# KitchenTimer_v2.net
KiCad netlist of a schematic drawn in EAGLE
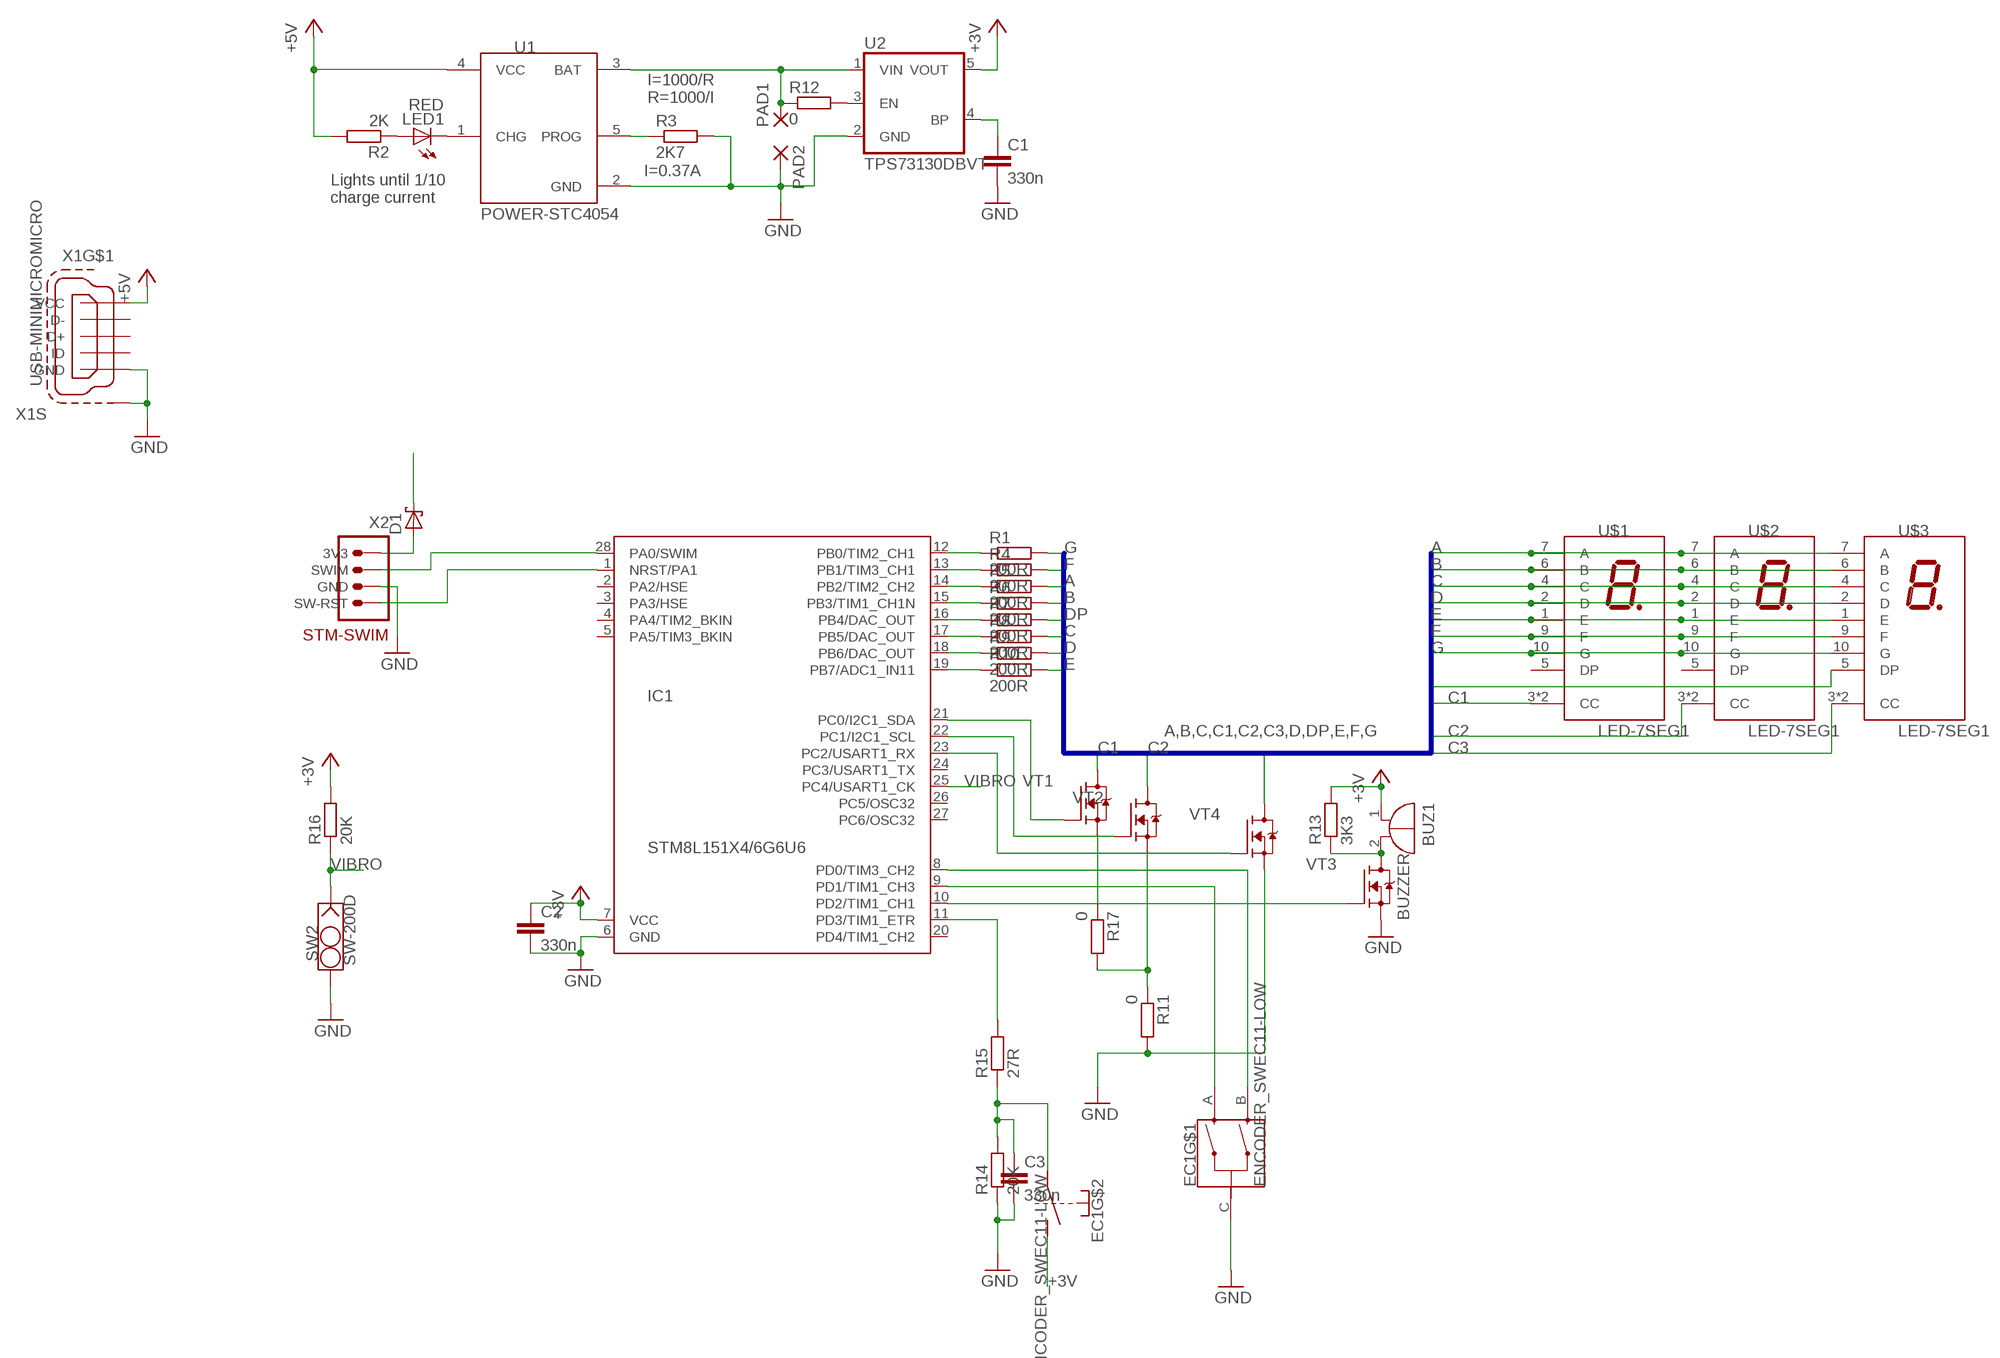
[diagram p0: schematic, sheet 1]

(export (version "E")
  (design (tool "Eeschema 10.0.6"))
  (components
    (comp (ref "BUZ1")
      (value "BUZZER")
      (footprint "eagle-import:PIEZO-D12_H9")
      (libsource (lib "eagle-import") (part "BUZZER"))
    )
    (comp (ref "C1")
      (value "330n")
      (footprint "eagle-import:CAP1206")
      (libsource (lib "eagle-import") (part "CAP_1206"))
    )
    (comp (ref "C2")
      (value "330n")
      (footprint "eagle-import:CAP1206")
      (libsource (lib "eagle-import") (part "CAP_1206"))
    )
    (comp (ref "C3")
      (value "330n")
      (footprint "eagle-import:CAP1206")
      (libsource (lib "eagle-import") (part "CAP_1206"))
    )
    (comp (ref "D1")
      (value "DIODE-SH_SOD523")
      (footprint "eagle-import:SODFL1608X65")
      (libsource (lib "eagle-import") (part "DIODE-SH_SOD523"))
    )
    (comp (ref "EC1")
      (value "ENCODER_SWEC11-LOW")
      (footprint "eagle-import:EC11E1544505")
      (libsource (lib "eagle-import") (part "ENCODER_SWEC11-LOW"))
    )
    (comp (ref "IC1")
      (value "STM8L151X4/6G6U6")
      (footprint "eagle-import:QFN28")
      (libsource (lib "eagle-import") (part "STM8L151X4/6G6U6"))
    )
    (comp (ref "LED1")
      (value "RED")
      (footprint "eagle-import:LED1206")
      (libsource (lib "eagle-import") (part "LED_1206"))
    )
    (comp (ref "PAD1")
      (value "1,6/0,9")
      (footprint "eagle-import:1,6_0,9")
      (libsource (lib "eagle-import") (part "1,6/0,9"))
    )
    (comp (ref "PAD2")
      (value "1,6/0,9")
      (footprint "eagle-import:1,6_0,9")
      (libsource (lib "eagle-import") (part "1,6/0,9"))
    )
    (comp (ref "R1")
      (value "200R")
      (footprint "eagle-import:RESC2012X50")
      (libsource (lib "eagle-import") (part "R_R0805"))
    )
    (comp (ref "R2")
      (value "2K")
      (footprint "eagle-import:RESC2012X50")
      (libsource (lib "eagle-import") (part "R_R0805"))
    )
    (comp (ref "R3")
      (value "2K7")
      (footprint "eagle-import:RESC2012X50")
      (libsource (lib "eagle-import") (part "R_R0805"))
    )
    (comp (ref "R4")
      (value "200R")
      (footprint "eagle-import:RESC2012X50")
      (libsource (lib "eagle-import") (part "R_R0805"))
    )
    (comp (ref "R5")
      (value "200R")
      (footprint "eagle-import:RESC2012X50")
      (libsource (lib "eagle-import") (part "R_R0805"))
    )
    (comp (ref "R6")
      (value "200R")
      (footprint "eagle-import:RESC2012X50")
      (libsource (lib "eagle-import") (part "R_R0805"))
    )
    (comp (ref "R7")
      (value "200R")
      (footprint "eagle-import:RESC2012X50")
      (libsource (lib "eagle-import") (part "R_R0805"))
    )
    (comp (ref "R8")
      (value "200R")
      (footprint "eagle-import:RESC2012X50")
      (libsource (lib "eagle-import") (part "R_R0805"))
    )
    (comp (ref "R9")
      (value "200R")
      (footprint "eagle-import:RESC2012X50")
      (libsource (lib "eagle-import") (part "R_R0805"))
    )
    (comp (ref "R10")
      (value "200R")
      (footprint "eagle-import:RESC2012X50")
      (libsource (lib "eagle-import") (part "R_R0805"))
    )
    (comp (ref "R11")
      (value "0")
      (footprint "eagle-import:RESC2012X50")
      (libsource (lib "eagle-import") (part "R_R0805"))
    )
    (comp (ref "R12")
      (value "0")
      (footprint "eagle-import:RESC2012X50")
      (libsource (lib "eagle-import") (part "R_R0805"))
    )
    (comp (ref "R13")
      (value "3K3")
      (footprint "eagle-import:RESC3216X60")
      (libsource (lib "eagle-import") (part "R_R1206"))
    )
    (comp (ref "R14")
      (value "20K")
      (footprint "eagle-import:RESC3216X60")
      (libsource (lib "eagle-import") (part "R_R1206"))
    )
    (comp (ref "R15")
      (value "27R")
      (footprint "eagle-import:RESC3216X60")
      (libsource (lib "eagle-import") (part "R_R1206"))
    )
    (comp (ref "R16")
      (value "20K")
      (footprint "eagle-import:RESC3216X60")
      (libsource (lib "eagle-import") (part "R_R1206"))
    )
    (comp (ref "R17")
      (value "0")
      (footprint "eagle-import:RESC2012X50")
      (libsource (lib "eagle-import") (part "R_R0805"))
    )
    (comp (ref "SW2")
      (value "SW-200D")
      (footprint "eagle-import:SW-200D")
      (libsource (lib "eagle-import") (part "SW-200D"))
    )
    (comp (ref "U$1")
      (value "LED-7SEG1")
      (footprint "eagle-import:LED-7SEG1")
      (libsource (lib "eagle-import") (part "LED-7SEG1"))
    )
    (comp (ref "U$2")
      (value "LED-7SEG1")
      (footprint "eagle-import:LED-7SEG1")
      (libsource (lib "eagle-import") (part "LED-7SEG1"))
    )
    (comp (ref "U$3")
      (value "LED-7SEG1")
      (footprint "eagle-import:LED-7SEG1")
      (libsource (lib "eagle-import") (part "LED-7SEG1"))
    )
    (comp (ref "U1")
      (value "POWER-STC4054")
      (footprint "eagle-import:SOT95P280X145-5")
      (libsource (lib "eagle-import") (part "POWER-STC4054"))
    )
    (comp (ref "U2")
      (value "TPS73130DBVT")
      (footprint "eagle-import:SOT95P280X145-5")
      (libsource (lib "eagle-import") (part "VREG-LD2985"))
    )
    (comp (ref "VT1")
      (value "FET-NSOT-23")
      (footprint "eagle-import:SOT95P240X115-3")
      (libsource (lib "eagle-import") (part "FET-NSOT-23"))
    )
    (comp (ref "VT2")
      (value "FET-NSOT-23")
      (footprint "eagle-import:SOT95P240X115-3")
      (libsource (lib "eagle-import") (part "FET-NSOT-23"))
    )
    (comp (ref "VT3")
      (value "FET-NSOT-23")
      (footprint "eagle-import:SOT95P240X115-3")
      (libsource (lib "eagle-import") (part "FET-NSOT-23"))
    )
    (comp (ref "VT4")
      (value "FET-NSOT-23")
      (footprint "eagle-import:SOT95P240X115-3")
      (libsource (lib "eagle-import") (part "FET-NSOT-23"))
    )
    (comp (ref "X1")
      (value "USB-MINIMICROMICRO")
      (footprint "eagle-import:USB-B-MICRO-SMD")
      (libsource (lib "eagle-import") (part "USB-MINIMICROMICRO"))
    )
    (comp (ref "X2")
      (value "STM-SWIMPOGOPADS")
      (footprint "eagle-import:SWIM-PADS-1.27")
      (libsource (lib "eagle-import") (part "STM-SWIMPOGOPADS"))
    )
  )
  (nets
    (net (code "1") (name "+3V") (class "Default")
      (node (ref "BUZ1") (pin "1") (pinfunction "+_1") (pintype "passive"))
      (node (ref "C2") (pin "1") (pinfunction "1_1") (pintype "passive"))
      (node (ref "D1") (pin "1") (pinfunction "C_1") (pintype "passive"))
      (node (ref "EC1") (pin "E") (pinfunction "2_E") (pintype "passive"))
      (node (ref "IC1") (pin "7") (pinfunction "VCC_7") (pintype "power_in"))
      (node (ref "R13") (pin "2") (pinfunction "2_2") (pintype "passive"))
      (node (ref "R16") (pin "2") (pinfunction "2_2") (pintype "passive"))
      (node (ref "U2") (pin "5") (pinfunction "VOUT_5") (pintype "passive"))
    )
    (net (code "2") (name "+5V") (class "Default")
      (node (ref "R2") (pin "2") (pinfunction "2_2") (pintype "passive"))
      (node (ref "U1") (pin "4") (pinfunction "VCC_4") (pintype "power_in"))
      (node (ref "X1") (pin "VBUS") (pinfunction "VCC_VBUS") (pintype "passive"))
    )
    (net (code "3") (name "/A") (class "Default")
      (node (ref "R5") (pin "2") (pinfunction "2_2") (pintype "passive"))
      (node (ref "U$1") (pin "7") (pinfunction "A_7") (pintype "bidirectional"))
      (node (ref "U$2") (pin "7") (pinfunction "A_7") (pintype "bidirectional"))
      (node (ref "U$3") (pin "7") (pinfunction "A_7") (pintype "bidirectional"))
    )
    (net (code "4") (name "/B") (class "Default")
      (node (ref "R6") (pin "2") (pinfunction "2_2") (pintype "passive"))
      (node (ref "U$1") (pin "6") (pinfunction "B_6") (pintype "bidirectional"))
      (node (ref "U$2") (pin "6") (pinfunction "B_6") (pintype "bidirectional"))
      (node (ref "U$3") (pin "6") (pinfunction "B_6") (pintype "bidirectional"))
    )
    (net (code "5") (name "/C") (class "Default")
      (node (ref "R8") (pin "2") (pinfunction "2_2") (pintype "passive"))
      (node (ref "U$1") (pin "4") (pinfunction "C_4") (pintype "bidirectional"))
      (node (ref "U$2") (pin "4") (pinfunction "C_4") (pintype "bidirectional"))
      (node (ref "U$3") (pin "4") (pinfunction "C_4") (pintype "bidirectional"))
    )
    (net (code "6") (name "/C1") (class "Default")
      (node (ref "U$1") (pin "3") (pinfunction "CC_3") (pintype "bidirectional"))
      (node (ref "U$1") (pin "8") (pinfunction "CC_8") (pintype "bidirectional"))
      (node (ref "VT1") (pin "3") (pinfunction "D_3") (pintype "passive"))
    )
    (net (code "7") (name "/C2") (class "Default")
      (node (ref "U$2") (pin "3") (pinfunction "CC_3") (pintype "bidirectional"))
      (node (ref "U$2") (pin "8") (pinfunction "CC_8") (pintype "bidirectional"))
      (node (ref "VT2") (pin "3") (pinfunction "D_3") (pintype "passive"))
    )
    (net (code "8") (name "/C3") (class "Default")
      (node (ref "U$3") (pin "3") (pinfunction "CC_3") (pintype "bidirectional"))
      (node (ref "U$3") (pin "8") (pinfunction "CC_8") (pintype "bidirectional"))
      (node (ref "VT4") (pin "3") (pinfunction "D_3") (pintype "passive"))
    )
    (net (code "9") (name "/D") (class "Default")
      (node (ref "R9") (pin "2") (pinfunction "2_2") (pintype "passive"))
      (node (ref "U$1") (pin "2") (pinfunction "D_2") (pintype "bidirectional"))
      (node (ref "U$2") (pin "2") (pinfunction "D_2") (pintype "bidirectional"))
      (node (ref "U$3") (pin "2") (pinfunction "D_2") (pintype "bidirectional"))
    )
    (net (code "10") (name "/DP") (class "Default")
      (node (ref "R7") (pin "2") (pinfunction "2_2") (pintype "passive"))
      (node (ref "U$3") (pin "5") (pinfunction "DP_5") (pintype "bidirectional"))
    )
    (net (code "11") (name "/E") (class "Default")
      (node (ref "R10") (pin "2") (pinfunction "2_2") (pintype "passive"))
      (node (ref "U$1") (pin "1") (pinfunction "E_1") (pintype "bidirectional"))
      (node (ref "U$2") (pin "1") (pinfunction "E_1") (pintype "bidirectional"))
      (node (ref "U$3") (pin "1") (pinfunction "E_1") (pintype "bidirectional"))
    )
    (net (code "12") (name "/F") (class "Default")
      (node (ref "R4") (pin "2") (pinfunction "2_2") (pintype "passive"))
      (node (ref "U$1") (pin "9") (pinfunction "F_9") (pintype "bidirectional"))
      (node (ref "U$2") (pin "9") (pinfunction "F_9") (pintype "bidirectional"))
      (node (ref "U$3") (pin "9") (pinfunction "F_9") (pintype "bidirectional"))
    )
    (net (code "13") (name "/G") (class "Default")
      (node (ref "R1") (pin "2") (pinfunction "2_2") (pintype "passive"))
      (node (ref "U$1") (pin "10") (pinfunction "G_10") (pintype "bidirectional"))
      (node (ref "U$2") (pin "10") (pinfunction "G_10") (pintype "bidirectional"))
      (node (ref "U$3") (pin "10") (pinfunction "G_10") (pintype "bidirectional"))
    )
    (net (code "14") (name "/VIBRO") (class "Default")
      (node (ref "IC1") (pin "25") (pinfunction "PC4/USART1_CK_25") (pintype "bidirectional"))
      (node (ref "R16") (pin "1") (pinfunction "1_1") (pintype "passive"))
      (node (ref "SW2") (pin "G") (pinfunction "G_G") (pintype "bidirectional"))
    )
    (net (code "15") (name "GND") (class "Default")
      (node (ref "C1") (pin "2") (pinfunction "2_2") (pintype "passive"))
      (node (ref "C2") (pin "2") (pinfunction "2_2") (pintype "passive"))
      (node (ref "C3") (pin "2") (pinfunction "2_2") (pintype "passive"))
      (node (ref "EC1") (pin "C") (pinfunction "C_C") (pintype "bidirectional"))
      (node (ref "IC1") (pin "6") (pinfunction "GND_6") (pintype "power_in"))
      (node (ref "PAD2") (pin "1") (pinfunction "P_1") (pintype "passive"))
      (node (ref "R11") (pin "2") (pinfunction "2_2") (pintype "passive"))
      (node (ref "R14") (pin "1") (pinfunction "1_1") (pintype "passive"))
      (node (ref "R3") (pin "2") (pinfunction "2_2") (pintype "passive"))
      (node (ref "SW2") (pin "S") (pinfunction "S_S") (pintype "bidirectional"))
      (node (ref "U1") (pin "2") (pinfunction "GND_2") (pintype "power_in"))
      (node (ref "U2") (pin "2") (pinfunction "GND_2") (pintype "passive"))
      (node (ref "VT3") (pin "2") (pinfunction "S_2") (pintype "passive"))
      (node (ref "VT4") (pin "2") (pinfunction "S_2") (pintype "passive"))
      (node (ref "X1") (pin "GND") (pinfunction "GND_GND") (pintype "passive"))
      (node (ref "X1") (pin "SHIELD1") (pinfunction "S1_SHIELD1") (pintype "passive"))
      (node (ref "X1") (pin "SHIELD2") (pinfunction "S1_SHIELD2") (pintype "passive"))
      (node (ref "X1") (pin "SHIELD3") (pinfunction "S1_SHIELD3") (pintype "passive"))
      (node (ref "X2") (pin "P$3") (pinfunction "GND_P$3") (pintype "passive"))
    )
    (net (code "16") (name "Net-(BUZ1--)") (class "Default")
      (node (ref "BUZ1") (pin "2") (pinfunction "-_2") (pintype "passive"))
      (node (ref "R13") (pin "1") (pinfunction "1_1") (pintype "passive"))
      (node (ref "VT3") (pin "3") (pinfunction "D_3") (pintype "passive"))
    )
    (net (code "17") (name "Net-(D1-A)") (class "Default")
      (node (ref "D1") (pin "2") (pinfunction "A_2") (pintype "passive"))
      (node (ref "X2") (pin "P$1") (pinfunction "3V3_P$1") (pintype "passive"))
    )
    (net (code "18") (name "Net-(EC1B-1)") (class "Default")
      (node (ref "C3") (pin "1") (pinfunction "1_1") (pintype "passive"))
      (node (ref "EC1") (pin "D") (pinfunction "1_D") (pintype "passive"))
      (node (ref "R14") (pin "2") (pinfunction "2_2") (pintype "passive"))
      (node (ref "R15") (pin "1") (pinfunction "1_1") (pintype "passive"))
    )
    (net (code "19") (name "Net-(IC1-NRST{slash}PA1)") (class "Default")
      (node (ref "IC1") (pin "1") (pinfunction "NRST/PA1_1") (pintype "bidirectional"))
      (node (ref "X2") (pin "P$4") (pinfunction "SW-RST_P$4") (pintype "passive"))
    )
    (net (code "20") (name "Net-(IC1-PA0{slash}SWIM)") (class "Default")
      (node (ref "IC1") (pin "28") (pinfunction "PA0/SWIM_28") (pintype "bidirectional"))
      (node (ref "X2") (pin "P$2") (pinfunction "SWIM_P$2") (pintype "passive"))
    )
    (net (code "21") (name "Net-(IC1-PB0{slash}TIM2_CH1)") (class "Default")
      (node (ref "IC1") (pin "12") (pinfunction "PB0/TIM2_CH1_12") (pintype "bidirectional"))
      (node (ref "R1") (pin "1") (pinfunction "1_1") (pintype "passive"))
    )
    (net (code "22") (name "Net-(IC1-PB1{slash}TIM3_CH1)") (class "Default")
      (node (ref "IC1") (pin "13") (pinfunction "PB1/TIM3_CH1_13") (pintype "bidirectional"))
      (node (ref "R4") (pin "1") (pinfunction "1_1") (pintype "passive"))
    )
    (net (code "23") (name "Net-(IC1-PB2{slash}TIM2_CH2)") (class "Default")
      (node (ref "IC1") (pin "14") (pinfunction "PB2/TIM2_CH2_14") (pintype "bidirectional"))
      (node (ref "R5") (pin "1") (pinfunction "1_1") (pintype "passive"))
    )
    (net (code "24") (name "Net-(IC1-PB3{slash}TIM1_CH1N)") (class "Default")
      (node (ref "IC1") (pin "15") (pinfunction "PB3/TIM1_CH1N_15") (pintype "bidirectional"))
      (node (ref "R6") (pin "1") (pinfunction "1_1") (pintype "passive"))
    )
    (net (code "25") (name "Net-(IC1-PB4{slash}DAC_OUT)") (class "Default")
      (node (ref "IC1") (pin "16") (pinfunction "PB4/DAC_OUT_16") (pintype "bidirectional"))
      (node (ref "R7") (pin "1") (pinfunction "1_1") (pintype "passive"))
    )
    (net (code "26") (name "Net-(IC1-PB5{slash}DAC_OUT)") (class "Default")
      (node (ref "IC1") (pin "17") (pinfunction "PB5/DAC_OUT_17") (pintype "bidirectional"))
      (node (ref "R8") (pin "1") (pinfunction "1_1") (pintype "passive"))
    )
    (net (code "27") (name "Net-(IC1-PB6{slash}DAC_OUT)") (class "Default")
      (node (ref "IC1") (pin "18") (pinfunction "PB6/DAC_OUT_18") (pintype "bidirectional"))
      (node (ref "R9") (pin "1") (pinfunction "1_1") (pintype "passive"))
    )
    (net (code "28") (name "Net-(IC1-PB7{slash}ADC1_IN11)") (class "Default")
      (node (ref "IC1") (pin "19") (pinfunction "PB7/ADC1_IN11_19") (pintype "bidirectional"))
      (node (ref "R10") (pin "1") (pinfunction "1_1") (pintype "passive"))
    )
    (net (code "29") (name "Net-(IC1-PC0{slash}I2C1_SDA)") (class "Default")
      (node (ref "IC1") (pin "21") (pinfunction "PC0/I2C1_SDA_21") (pintype "bidirectional"))
      (node (ref "VT1") (pin "1") (pinfunction "G_1") (pintype "passive"))
    )
    (net (code "30") (name "Net-(IC1-PC1{slash}I2C1_SCL)") (class "Default")
      (node (ref "IC1") (pin "22") (pinfunction "PC1/I2C1_SCL_22") (pintype "bidirectional"))
      (node (ref "VT2") (pin "1") (pinfunction "G_1") (pintype "passive"))
    )
    (net (code "31") (name "Net-(IC1-PC2{slash}USART1_RX)") (class "Default")
      (node (ref "IC1") (pin "23") (pinfunction "PC2/USART1_RX_23") (pintype "bidirectional"))
      (node (ref "VT4") (pin "1") (pinfunction "G_1") (pintype "passive"))
    )
    (net (code "32") (name "Net-(IC1-PD0{slash}TIM3_CH2)") (class "Default")
      (node (ref "EC1") (pin "B") (pinfunction "B_B") (pintype "bidirectional"))
      (node (ref "IC1") (pin "8") (pinfunction "PD0/TIM3_CH2_8") (pintype "bidirectional"))
    )
    (net (code "33") (name "Net-(IC1-PD1{slash}TIM1_CH3)") (class "Default")
      (node (ref "EC1") (pin "A") (pinfunction "A_A") (pintype "bidirectional"))
      (node (ref "IC1") (pin "9") (pinfunction "PD1/TIM1_CH3_9") (pintype "bidirectional"))
    )
    (net (code "34") (name "Net-(IC1-PD2{slash}TIM1_CH1)") (class "Default")
      (node (ref "IC1") (pin "10") (pinfunction "PD2/TIM1_CH1_10") (pintype "bidirectional"))
      (node (ref "VT3") (pin "1") (pinfunction "G_1") (pintype "passive"))
    )
    (net (code "35") (name "Net-(IC1-PD3{slash}TIM1_ETR)") (class "Default")
      (node (ref "IC1") (pin "11") (pinfunction "PD3/TIM1_ETR_11") (pintype "bidirectional"))
      (node (ref "R15") (pin "2") (pinfunction "2_2") (pintype "passive"))
    )
    (net (code "36") (name "Net-(LED1-PadA)") (class "Default")
      (node (ref "LED1") (pin "A") (pinfunction "A_A") (pintype "passive"))
      (node (ref "R2") (pin "1") (pinfunction "1_1") (pintype "passive"))
    )
    (net (code "37") (name "Net-(PAD1-P)") (class "Default")
      (node (ref "PAD1") (pin "1") (pinfunction "P_1") (pintype "passive"))
      (node (ref "R12") (pin "1") (pinfunction "1_1") (pintype "passive"))
      (node (ref "U1") (pin "3") (pinfunction "BAT_3") (pintype "bidirectional"))
      (node (ref "U2") (pin "1") (pinfunction "VIN_1") (pintype "input"))
    )
    (net (code "38") (name "Net-(U1-CHG)") (class "Default")
      (node (ref "LED1") (pin "C") (pinfunction "C_C") (pintype "passive"))
      (node (ref "U1") (pin "1") (pinfunction "CHG_1") (pintype "output"))
    )
    (net (code "39") (name "Net-(U1-PROG)") (class "Default")
      (node (ref "R3") (pin "1") (pinfunction "1_1") (pintype "passive"))
      (node (ref "U1") (pin "5") (pinfunction "PROG_5") (pintype "bidirectional"))
    )
    (net (code "40") (name "Net-(U2-BP)") (class "Default")
      (node (ref "C1") (pin "1") (pinfunction "1_1") (pintype "passive"))
      (node (ref "U2") (pin "4") (pinfunction "BP_4") (pintype "input"))
    )
    (net (code "41") (name "Net-(U2-EN)") (class "Default")
      (node (ref "R12") (pin "2") (pinfunction "2_2") (pintype "passive"))
      (node (ref "U2") (pin "3") (pinfunction "EN_3") (pintype "input"))
    )
    (net (code "42") (name "Net-(VT1-S)") (class "Default")
      (node (ref "R17") (pin "1") (pinfunction "1_1") (pintype "passive"))
      (node (ref "VT1") (pin "2") (pinfunction "S_2") (pintype "passive"))
    )
    (net (code "43") (name "Net-(VT2-S)") (class "Default")
      (node (ref "R11") (pin "1") (pinfunction "1_1") (pintype "passive"))
      (node (ref "R17") (pin "2") (pinfunction "2_2") (pintype "passive"))
      (node (ref "VT2") (pin "2") (pinfunction "S_2") (pintype "passive"))
    )
    (net (code "44") (name "unconnected-(IC1-PA2{slash}HSE-Pad2)") (class "Default")
      (node (ref "IC1") (pin "2") (pinfunction "PA2/HSE_2") (pintype "bidirectional"))
    )
    (net (code "45") (name "unconnected-(IC1-PA3{slash}HSE-Pad3)") (class "Default")
      (node (ref "IC1") (pin "3") (pinfunction "PA3/HSE_3") (pintype "bidirectional"))
    )
    (net (code "46") (name "unconnected-(IC1-PA4{slash}TIM2_BKIN-Pad4)") (class "Default")
      (node (ref "IC1") (pin "4") (pinfunction "PA4/TIM2_BKIN_4") (pintype "bidirectional"))
    )
    (net (code "47") (name "unconnected-(IC1-PA5{slash}TIM3_BKIN-Pad5)") (class "Default")
      (node (ref "IC1") (pin "5") (pinfunction "PA5/TIM3_BKIN_5") (pintype "bidirectional"))
    )
    (net (code "48") (name "unconnected-(IC1-PC3{slash}USART1_TX-Pad24)") (class "Default")
      (node (ref "IC1") (pin "24") (pinfunction "PC3/USART1_TX_24") (pintype "bidirectional"))
    )
    (net (code "49") (name "unconnected-(IC1-PC5{slash}OSC32-Pad26)") (class "Default")
      (node (ref "IC1") (pin "26") (pinfunction "PC5/OSC32_26") (pintype "bidirectional"))
    )
    (net (code "50") (name "unconnected-(IC1-PC6{slash}OSC32-Pad27)") (class "Default")
      (node (ref "IC1") (pin "27") (pinfunction "PC6/OSC32_27") (pintype "bidirectional"))
    )
    (net (code "51") (name "unconnected-(IC1-PD4{slash}TIM1_CH2-Pad20)") (class "Default")
      (node (ref "IC1") (pin "20") (pinfunction "PD4/TIM1_CH2_20") (pintype "bidirectional"))
    )
    (net (code "52") (name "unconnected-(U$1-DP-Pad5)") (class "Default")
      (node (ref "U$1") (pin "5") (pinfunction "DP_5") (pintype "bidirectional"))
    )
    (net (code "53") (name "unconnected-(U$2-DP-Pad5)") (class "Default")
      (node (ref "U$2") (pin "5") (pinfunction "DP_5") (pintype "bidirectional"))
    )
    (net (code "54") (name "unconnected-(X1-PadD+)") (class "Default")
      (node (ref "X1") (pin "D+") (pinfunction "D+_D+") (pintype "passive"))
    )
    (net (code "55") (name "unconnected-(X1-PadD-)") (class "Default")
      (node (ref "X1") (pin "D-") (pinfunction "D-_D-") (pintype "passive"))
    )
    (net (code "56") (name "unconnected-(X1-PadID)") (class "Default")
      (node (ref "X1") (pin "ID") (pinfunction "ID_ID") (pintype "passive"))
    )
  )
)
